# Enclosure_130x95_BPHC.net
KiCad netlist of a schematic drawn in EAGLE
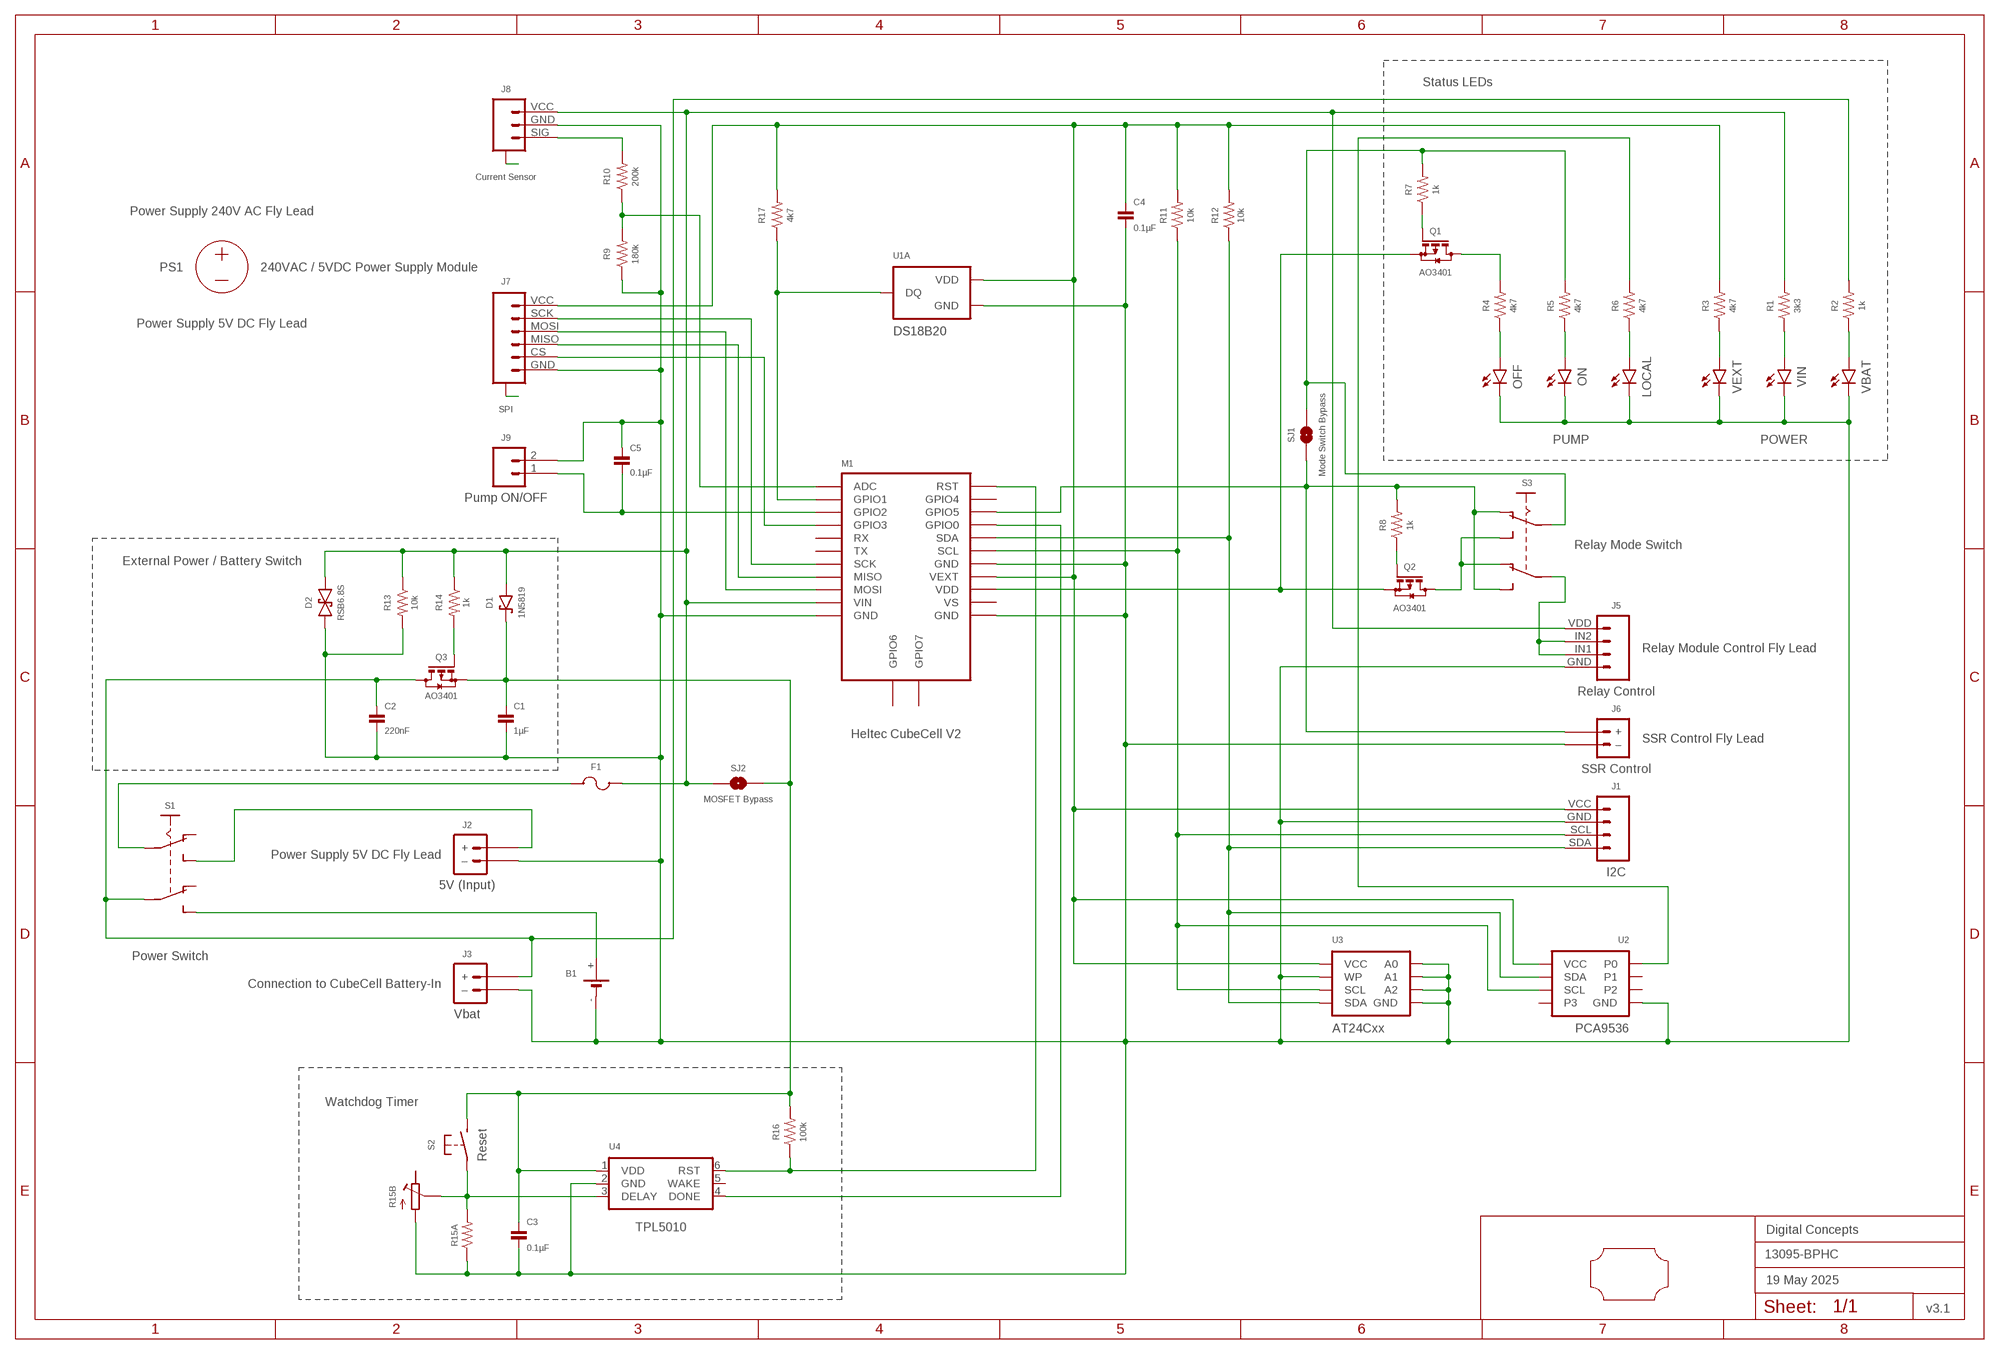
[diagram p0: schematic, sheet 1]

(export (version "E")
  (design (tool "Eeschema 10.0.6"))
  (components
    (comp (ref "B1")
      (value "BATTERY-HOLDER-14500(AA)")
      (footprint "eagle-import:BATTERY-14500")
      (libsource (lib "eagle-import") (part "BATTERY-HOLDER-14500(AA)"))
    )
    (comp (ref "C1")
      (value "1µF")
      (footprint "eagle-import:C0805")
      (libsource (lib "eagle-import") (part "CAPACITOR-0805"))
    )
    (comp (ref "C2")
      (value "220nF")
      (footprint "eagle-import:C0805")
      (libsource (lib "eagle-import") (part "CAPACITOR-0805"))
    )
    (comp (ref "C3")
      (value "0.1µF")
      (footprint "eagle-import:C0805")
      (libsource (lib "eagle-import") (part "CAPACITOR-0805"))
    )
    (comp (ref "C4")
      (value "0.1µF")
      (footprint "eagle-import:C0805")
      (libsource (lib "eagle-import") (part "CAPACITOR-0805"))
    )
    (comp (ref "C5")
      (value "0.1µF")
      (footprint "eagle-import:C0805")
      (libsource (lib "eagle-import") (part "CAPACITOR-0805"))
    )
    (comp (ref "D1")
      (value "1N5819")
      (footprint "eagle-import:SOD-123")
      (libsource (lib "eagle-import") (part "DIODE-SCHOTTKY-1N5819"))
    )
    (comp (ref "D2")
      (value "RSB6.8S")
      (footprint "eagle-import:VMD2")
      (libsource (lib "eagle-import") (part "DIODE-SCHOTTKY-BIDIRECTIONAL"))
    )
    (comp (ref "F1")
      (value "Fuse")
      (footprint "eagle-import:F0805")
      (libsource (lib "eagle-import") (part "MF-PSMF050X-2"))
    )
    (comp (ref "J1")
      (value "I2C")
      (footprint "eagle-import:CONN_04-I2C")
      (libsource (lib "eagle-import") (part "HEADER-1X4-I2C"))
    )
    (comp (ref "J2")
      (value "5V (Input)")
      (footprint "eagle-import:JST-PH2.0-2-VERTICAL-POWER")
      (libsource (lib "eagle-import") (part "JST-PH2.0-2-VERTICAL-POWER"))
    )
    (comp (ref "J3")
      (value "Vbat")
      (footprint "eagle-import:JST-GH1.25-2-HORIZONTAL")
      (libsource (lib "eagle-import") (part "JST-GH1.25-2-HORIZONTAL-POWER"))
    )
    (comp (ref "J5")
      (value "Relay Control")
      (footprint "eagle-import:JST-PH2.0-4-HORIZONTAL-RELAY")
      (libsource (lib "eagle-import") (part "JST-PH2.0-4-HORIZONTAL-RELAY"))
    )
    (comp (ref "J6")
      (value "SSR Control")
      (footprint "eagle-import:JST-PH2.0-2-HORIZONTAL-POWER")
      (libsource (lib "eagle-import") (part "JST-PH2.0-2-H-POWER"))
    )
    (comp (ref "J7")
      (value "SPI")
      (footprint "eagle-import:JST-SH1.0-6-HORIZONTAL-SPI")
      (libsource (lib "eagle-import") (part "JST-SH1.0-6-SMD-HORIZONTAL-SPI"))
    )
    (comp (ref "J8")
      (value "Current Sensor")
      (footprint "eagle-import:JST-SH1.0-3-HORIZONTAL-SIG")
      (libsource (lib "eagle-import") (part "JST-SH1.0-3-SMD-HORIZONTAL-SIG"))
    )
    (comp (ref "J9")
      (value "Pump ON/OFF")
      (footprint "eagle-import:CONN_02-GENERIC")
      (libsource (lib "eagle-import") (part "HEADER-1X2-GENERIC"))
    )
    (comp (ref "LOCAL")
      (value "LEDCHIP-LED0805")
      (footprint "eagle-import:CHIP-LED0805")
      (libsource (lib "eagle-import") (part "LEDCHIP-LED0805"))
    )
    (comp (ref "M1")
      (value "Heltec CubeCell V2")
      (footprint "eagle-import:HELTEC-CUBECELL")
      (libsource (lib "eagle-import") (part "HELTEC-CUBECELL"))
    )
    (comp (ref "OFF")
      (value "LEDCHIP-LED0805")
      (footprint "eagle-import:CHIP-LED0805")
      (libsource (lib "eagle-import") (part "LEDCHIP-LED0805"))
    )
    (comp (ref "ON")
      (value "LEDCHIP-LED0805")
      (footprint "eagle-import:CHIP-LED0805")
      (libsource (lib "eagle-import") (part "LEDCHIP-LED0805"))
    )
    (comp (ref "PCB1")
      (value "PCB-OUTLINE-130X95-HALF-TOP")
      (footprint "eagle-import:PROTO-130X95-OUTLINE-HALF-TOP")
      (libsource (lib "eagle-import") (part "PCB-OUTLINE-130X95-HALF-TOP"))
    )
    (comp (ref "PS1")
      (value "240VAC / 5VDC Power Supply Module")
      (footprint "eagle-import:AC_DC_POWER_SUPPLY")
      (libsource (lib "eagle-import") (part "POWER_SUPPLY_MODULE"))
    )
    (comp (ref "Q1")
      (value "AO3401")
      (footprint "eagle-import:SOT-23")
      (libsource (lib "eagle-import") (part "MOSFET-AO3401"))
    )
    (comp (ref "Q2")
      (value "AO3401")
      (footprint "eagle-import:SOT-23")
      (libsource (lib "eagle-import") (part "MOSFET-AO3401"))
    )
    (comp (ref "Q3")
      (value "AO3401")
      (footprint "eagle-import:SOT-23")
      (libsource (lib "eagle-import") (part "MOSFET-AO3401"))
    )
    (comp (ref "R1")
      (value "3k3")
      (footprint "eagle-import:R0805")
      (libsource (lib "eagle-import") (part "RESISTORR0805"))
    )
    (comp (ref "R2")
      (value "1k")
      (footprint "eagle-import:R0805")
      (libsource (lib "eagle-import") (part "RESISTORR0805"))
    )
    (comp (ref "R3")
      (value "4k7")
      (footprint "eagle-import:R0805")
      (libsource (lib "eagle-import") (part "RESISTORR0805"))
    )
    (comp (ref "R4")
      (value "4k7")
      (footprint "eagle-import:R0805")
      (libsource (lib "eagle-import") (part "RESISTORR0805"))
    )
    (comp (ref "R5")
      (value "4k7")
      (footprint "eagle-import:R0805")
      (libsource (lib "eagle-import") (part "RESISTORR0805"))
    )
    (comp (ref "R6")
      (value "4k7")
      (footprint "eagle-import:R0805")
      (libsource (lib "eagle-import") (part "RESISTORR0805"))
    )
    (comp (ref "R7")
      (value "1k")
      (footprint "eagle-import:R0805")
      (libsource (lib "eagle-import") (part "RESISTORR0805"))
    )
    (comp (ref "R8")
      (value "1k")
      (footprint "eagle-import:R0805")
      (libsource (lib "eagle-import") (part "RESISTORR0805"))
    )
    (comp (ref "R9")
      (value "180k")
      (footprint "eagle-import:R0805")
      (libsource (lib "eagle-import") (part "RESISTORR0805"))
    )
    (comp (ref "R10")
      (value "200k")
      (footprint "eagle-import:R0805")
      (libsource (lib "eagle-import") (part "RESISTORR0805"))
    )
    (comp (ref "R11")
      (value "10k")
      (footprint "eagle-import:R0805")
      (libsource (lib "eagle-import") (part "RESISTORR0805"))
    )
    (comp (ref "R12")
      (value "10k")
      (footprint "eagle-import:R0805")
      (libsource (lib "eagle-import") (part "RESISTORR0805"))
    )
    (comp (ref "R13")
      (value "10k")
      (footprint "eagle-import:R0805")
      (libsource (lib "eagle-import") (part "RESISTORR0805"))
    )
    (comp (ref "R14")
      (value "1k")
      (footprint "eagle-import:R0805")
      (libsource (lib "eagle-import") (part "RESISTORR0805"))
    )
    (comp (ref "R15A")
      (value "RESISTORR0805")
      (footprint "eagle-import:R0805")
      (libsource (lib "eagle-import") (part "RESISTORR0805"))
    )
    (comp (ref "R15B")
      (value "RESISTOR-TRIMM-33")
      (footprint "eagle-import:RTRIM3_3")
      (libsource (lib "eagle-import") (part "RESISTOR-TRIMM-33"))
    )
    (comp (ref "R16")
      (value "100k")
      (footprint "eagle-import:R0805")
      (libsource (lib "eagle-import") (part "RESISTORR0805"))
    )
    (comp (ref "R17")
      (value "4k7")
      (footprint "eagle-import:R0805")
      (libsource (lib "eagle-import") (part "RESISTORR0805"))
    )
    (comp (ref "S1")
      (value "Power Switch")
      (footprint "eagle-import:SWITCH-DPDT-PTH")
      (libsource (lib "eagle-import") (part "SWITCH-SLIDE-DPDT-PTH"))
    )
    (comp (ref "S2")
      (value "Reset")
      (footprint "eagle-import:SWITCH-2-PAD")
      (libsource (lib "eagle-import") (part "SWITCH-MOMENTARY-2-PIN"))
    )
    (comp (ref "S3")
      (value "Relay Mode Switch")
      (footprint "eagle-import:SWITCH-DPDT-SMD")
      (libsource (lib "eagle-import") (part "SWITCH-SLIDE-DPDT-SMT"))
    )
    (comp (ref "SJ1")
      (value "Mode Switch Bypass")
      (footprint "eagle-import:SJ")
      (libsource (lib "eagle-import") (part "SJ"))
    )
    (comp (ref "SJ2")
      (value "MOSFET Bypass")
      (footprint "eagle-import:SJ")
      (libsource (lib "eagle-import") (part "SJ"))
    )
    (comp (ref "U1A")
      (value "DS18B20")
      (footprint "eagle-import:TO-92")
      (fields (field (name "MF") "Maxim Integrated"))
      (libsource (lib "eagle-import") (part "THERMOMETER-DS18B20"))
    )
    (comp (ref "U2")
      (value "PCA9536")
      (footprint "eagle-import:SOP-8")
      (libsource (lib "eagle-import") (part "PCA9536-I2C-GPIO4"))
    )
    (comp (ref "U3")
      (value "AT24Cxx")
      (footprint "eagle-import:SOP-8")
      (libsource (lib "eagle-import") (part "AT24CXX-EEPROM"))
    )
    (comp (ref "U4")
      (value "TPL5010")
      (footprint "eagle-import:SOT-23-6")
      (libsource (lib "eagle-import") (part "TPL5010DDCR"))
    )
    (comp (ref "VBAT")
      (value "LEDCHIP-LED0805")
      (footprint "eagle-import:CHIP-LED0805")
      (libsource (lib "eagle-import") (part "LEDCHIP-LED0805"))
    )
    (comp (ref "VEXT")
      (value "LEDCHIP-LED0805")
      (footprint "eagle-import:CHIP-LED0805")
      (libsource (lib "eagle-import") (part "LEDCHIP-LED0805"))
    )
    (comp (ref "VIN")
      (value "LEDCHIP-LED0805")
      (footprint "eagle-import:CHIP-LED0805")
      (libsource (lib "eagle-import") (part "LEDCHIP-LED0805"))
    )
  )
  (nets
    (net (code "1") (name "Net-(C5-Pad2)") (class "Default")
      (node (ref "C5") (pin "2") (pinfunction "2_2") (pintype "passive"))
      (node (ref "J9") (pin "1") (pinfunction "1_1") (pintype "passive"))
      (node (ref "M1") (pin "GPIO2") (pinfunction "GPIO2_GPIO2") (pintype "bidirectional"))
    )
    (net (code "2") (name "Net-(D2-1)") (class "Default")
      (node (ref "D1") (pin "A") (pinfunction "A_A") (pintype "passive"))
      (node (ref "D2") (pin "P$1") (pinfunction "1_P$1") (pintype "passive"))
      (node (ref "F1") (pin "1") (pinfunction "1_1") (pintype "passive"))
      (node (ref "J5") (pin "VDD") (pinfunction "1_VDD") (pintype "passive"))
      (node (ref "J8") (pin "VCC") (pinfunction "3_VCC") (pintype "passive"))
      (node (ref "M1") (pin "VIN") (pinfunction "VIN_VIN") (pintype "bidirectional"))
      (node (ref "R1") (pin "2") (pinfunction "2_2") (pintype "passive"))
      (node (ref "R13") (pin "1") (pinfunction "1_1") (pintype "passive"))
      (node (ref "R14") (pin "1") (pinfunction "1_1") (pintype "passive"))
      (node (ref "SJ2") (pin "1") (pinfunction "1_1") (pintype "passive"))
    )
    (net (code "3") (name "Net-(D2-2)") (class "Default")
      (node (ref "B1") (pin "-") (pinfunction "-_-") (pintype "power_in"))
      (node (ref "C1") (pin "2") (pinfunction "2_2") (pintype "passive"))
      (node (ref "C2") (pin "2") (pinfunction "2_2") (pintype "passive"))
      (node (ref "C3") (pin "2") (pinfunction "2_2") (pintype "passive"))
      (node (ref "C4") (pin "2") (pinfunction "2_2") (pintype "passive"))
      (node (ref "C5") (pin "1") (pinfunction "1_1") (pintype "passive"))
      (node (ref "D2") (pin "P$2") (pinfunction "2_P$2") (pintype "passive"))
      (node (ref "J1") (pin "GND") (pinfunction "2_GND") (pintype "passive"))
      (node (ref "J2") (pin "-") (pinfunction "–_-") (pintype "power_in"))
      (node (ref "J3") (pin "-") (pinfunction "–_-") (pintype "power_in"))
      (node (ref "J5") (pin "GND") (pinfunction "4_GND") (pintype "passive"))
      (node (ref "J6") (pin "-") (pinfunction "–_-") (pintype "power_in"))
      (node (ref "J7") (pin "GND") (pinfunction "1_GND") (pintype "passive"))
      (node (ref "J8") (pin "GND") (pinfunction "2_GND") (pintype "passive"))
      (node (ref "J9") (pin "2") (pinfunction "2_2") (pintype "passive"))
      (node (ref "LOCAL") (pin "C") (pinfunction "C_C") (pintype "passive"))
      (node (ref "M1") (pin "GND@11") (pinfunction "GND_GND@11") (pintype "bidirectional"))
      (node (ref "M1") (pin "GND@14") (pinfunction "GND_GND@14") (pintype "bidirectional"))
      (node (ref "M1") (pin "GND@18") (pinfunction "GND_GND@18") (pintype "bidirectional"))
      (node (ref "OFF") (pin "C") (pinfunction "C_C") (pintype "passive"))
      (node (ref "ON") (pin "C") (pinfunction "C_C") (pintype "passive"))
      (node (ref "R13") (pin "2") (pinfunction "2_2") (pintype "passive"))
      (node (ref "R15A") (pin "1") (pinfunction "1_1") (pintype "passive"))
      (node (ref "R15B") (pin "1") (pinfunction "A_1") (pintype "passive"))
      (node (ref "R9") (pin "1") (pinfunction "1_1") (pintype "passive"))
      (node (ref "U1A") (pin "1") (pinfunction "GND_1") (pintype "power_in"))
      (node (ref "U2") (pin "4") (pinfunction "GND_4") (pintype "power_in"))
      (node (ref "U3") (pin "1") (pinfunction "A0_1") (pintype "bidirectional"))
      (node (ref "U3") (pin "2") (pinfunction "A1_2") (pintype "bidirectional"))
      (node (ref "U3") (pin "3") (pinfunction "A2_3") (pintype "bidirectional"))
      (node (ref "U3") (pin "4") (pinfunction "GND_4") (pintype "bidirectional"))
      (node (ref "U3") (pin "7") (pinfunction "WP_7") (pintype "bidirectional"))
      (node (ref "U4") (pin "2") (pinfunction "GND_2") (pintype "power_in"))
      (node (ref "VBAT") (pin "C") (pinfunction "C_C") (pintype "passive"))
      (node (ref "VEXT") (pin "C") (pinfunction "C_C") (pintype "passive"))
      (node (ref "VIN") (pin "C") (pinfunction "C_C") (pintype "passive"))
    )
    (net (code "4") (name "Net-(J1-1)") (class "Default")
      (node (ref "C4") (pin "1") (pinfunction "1_1") (pintype "passive"))
      (node (ref "J1") (pin "VCC") (pinfunction "1_VCC") (pintype "passive"))
      (node (ref "J7") (pin "VCC") (pinfunction "6_VCC") (pintype "passive"))
      (node (ref "M1") (pin "VEXT") (pinfunction "VEXT_VEXT") (pintype "bidirectional"))
      (node (ref "R11") (pin "2") (pinfunction "2_2") (pintype "passive"))
      (node (ref "R12") (pin "2") (pinfunction "2_2") (pintype "passive"))
      (node (ref "R17") (pin "2") (pinfunction "2_2") (pintype "passive"))
      (node (ref "R3") (pin "2") (pinfunction "2_2") (pintype "passive"))
      (node (ref "U1A") (pin "3") (pinfunction "VDD_3") (pintype "power_in"))
      (node (ref "U2") (pin "8") (pinfunction "VCC_8") (pintype "power_in"))
      (node (ref "U3") (pin "8") (pinfunction "VCC_8") (pintype "bidirectional"))
    )
    (net (code "5") (name "Net-(J1-3)") (class "Default")
      (node (ref "J1") (pin "SCL") (pinfunction "3_SCL") (pintype "passive"))
      (node (ref "M1") (pin "SCL") (pinfunction "SCL_SCL") (pintype "bidirectional"))
      (node (ref "R11") (pin "1") (pinfunction "1_1") (pintype "passive"))
      (node (ref "U2") (pin "6") (pinfunction "SCL_6") (pintype "bidirectional"))
      (node (ref "U3") (pin "6") (pinfunction "SCL_6") (pintype "bidirectional"))
    )
    (net (code "6") (name "Net-(J1-4)") (class "Default")
      (node (ref "J1") (pin "SDA") (pinfunction "4_SDA") (pintype "passive"))
      (node (ref "M1") (pin "SDA") (pinfunction "SDA_SDA") (pintype "bidirectional"))
      (node (ref "R12") (pin "1") (pinfunction "1_1") (pintype "passive"))
      (node (ref "U2") (pin "7") (pinfunction "SDA_7") (pintype "bidirectional"))
      (node (ref "U3") (pin "5") (pinfunction "SDA_5") (pintype "bidirectional"))
    )
    (net (code "7") (name "Net-(J5-2)") (class "Default")
      (node (ref "J5") (pin "IN1") (pinfunction "3_IN1") (pintype "passive"))
      (node (ref "J5") (pin "IN2") (pinfunction "2_IN2") (pintype "passive"))
      (node (ref "S3") (pin "P$5") (pinfunction "P2_P$5") (pintype "passive"))
    )
    (net (code "8") (name "Net-(J7-2)") (class "Default")
      (node (ref "J7") (pin "CS") (pinfunction "2_CS") (pintype "passive"))
      (node (ref "M1") (pin "GPIO3") (pinfunction "GPIO3_GPIO3") (pintype "bidirectional"))
    )
    (net (code "9") (name "Net-(J7-3)") (class "Default")
      (node (ref "J7") (pin "MISO") (pinfunction "3_MISO") (pintype "passive"))
      (node (ref "M1") (pin "MISO") (pinfunction "MISO_MISO") (pintype "bidirectional"))
    )
    (net (code "10") (name "Net-(J7-4)") (class "Default")
      (node (ref "J7") (pin "MOSI") (pinfunction "4_MOSI") (pintype "passive"))
      (node (ref "M1") (pin "MOSI") (pinfunction "MOSI_MOSI") (pintype "bidirectional"))
    )
    (net (code "11") (name "Net-(J7-5)") (class "Default")
      (node (ref "J7") (pin "SCK") (pinfunction "5_SCK") (pintype "passive"))
      (node (ref "M1") (pin "SCK") (pinfunction "SCK_SCK") (pintype "bidirectional"))
    )
    (net (code "12") (name "Net-(J7-A-PadA@1)") (class "Default")
      (node (ref "J7") (pin "A@1") (pinfunction "A_A@1") (pintype "power_in"))
      (node (ref "J7") (pin "A@6") (pinfunction "A_A@6") (pintype "power_in"))
    )
    (net (code "13") (name "Net-(J8-1)") (class "Default")
      (node (ref "J8") (pin "SIG") (pinfunction "1_SIG") (pintype "passive"))
      (node (ref "R10") (pin "2") (pinfunction "2_2") (pintype "passive"))
    )
    (net (code "14") (name "Net-(J8-A-PadA@1)") (class "Default")
      (node (ref "J8") (pin "A@1") (pinfunction "A_A@1") (pintype "power_in"))
      (node (ref "J8") (pin "A@3") (pinfunction "A_A@3") (pintype "power_in"))
    )
    (net (code "15") (name "Net-(LOCAL-PadA)") (class "Default")
      (node (ref "LOCAL") (pin "A") (pinfunction "A_A") (pintype "passive"))
      (node (ref "R6") (pin "1") (pinfunction "1_1") (pintype "passive"))
    )
    (net (code "16") (name "Net-(M1-PadADC)") (class "Default")
      (node (ref "M1") (pin "ADC") (pinfunction "ADC_ADC") (pintype "bidirectional"))
      (node (ref "R10") (pin "1") (pinfunction "1_1") (pintype "passive"))
      (node (ref "R9") (pin "2") (pinfunction "2_2") (pintype "passive"))
    )
    (net (code "17") (name "Net-(OFF-PadA)") (class "Default")
      (node (ref "OFF") (pin "A") (pinfunction "A_A") (pintype "passive"))
      (node (ref "R4") (pin "1") (pinfunction "1_1") (pintype "passive"))
    )
    (net (code "18") (name "Net-(ON-PadA)") (class "Default")
      (node (ref "ON") (pin "A") (pinfunction "A_A") (pintype "passive"))
      (node (ref "R5") (pin "1") (pinfunction "1_1") (pintype "passive"))
    )
    (net (code "19") (name "Net-(Q1-D)") (class "Default")
      (node (ref "Q1") (pin "3") (pinfunction "D_3") (pintype "passive"))
      (node (ref "R4") (pin "2") (pinfunction "2_2") (pintype "passive"))
    )
    (net (code "20") (name "Net-(Q1-G)") (class "Default")
      (node (ref "Q1") (pin "1") (pinfunction "G_1") (pintype "passive"))
      (node (ref "R7") (pin "1") (pinfunction "1_1") (pintype "passive"))
    )
    (net (code "21") (name "Net-(Q1-S)") (class "Default")
      (node (ref "M1") (pin "VDD") (pinfunction "VDD_VDD") (pintype "bidirectional"))
      (node (ref "Q1") (pin "2") (pinfunction "S_2") (pintype "passive"))
      (node (ref "Q2") (pin "2") (pinfunction "S_2") (pintype "passive"))
    )
    (net (code "22") (name "Net-(Q2-D)") (class "Default")
      (node (ref "Q2") (pin "3") (pinfunction "D_3") (pintype "passive"))
      (node (ref "S3") (pin "P$3") (pinfunction "S1_P$3") (pintype "passive"))
      (node (ref "S3") (pin "P$4") (pinfunction "O2_P$4") (pintype "passive"))
    )
    (net (code "23") (name "Net-(Q2-G)") (class "Default")
      (node (ref "Q2") (pin "1") (pinfunction "G_1") (pintype "passive"))
      (node (ref "R8") (pin "1") (pinfunction "1_1") (pintype "passive"))
    )
    (net (code "24") (name "Net-(Q3-D)") (class "Default")
      (node (ref "C2") (pin "1") (pinfunction "1_1") (pintype "passive"))
      (node (ref "J3") (pin "+") (pinfunction "+_+") (pintype "power_in"))
      (node (ref "Q3") (pin "3") (pinfunction "D_3") (pintype "passive"))
      (node (ref "R2") (pin "2") (pinfunction "2_2") (pintype "passive"))
      (node (ref "S1") (pin "P$5") (pinfunction "P2_P$5") (pintype "passive"))
    )
    (net (code "25") (name "Net-(Q3-G)") (class "Default")
      (node (ref "Q3") (pin "1") (pinfunction "G_1") (pintype "passive"))
      (node (ref "R14") (pin "2") (pinfunction "2_2") (pintype "passive"))
    )
    (net (code "26") (name "Net-(Q3-S)") (class "Default")
      (node (ref "C1") (pin "1") (pinfunction "1_1") (pintype "passive"))
      (node (ref "C3") (pin "1") (pinfunction "1_1") (pintype "passive"))
      (node (ref "D1") (pin "C") (pinfunction "C_C") (pintype "passive"))
      (node (ref "Q3") (pin "2") (pinfunction "S_2") (pintype "passive"))
      (node (ref "R16") (pin "2") (pinfunction "2_2") (pintype "passive"))
      (node (ref "S2") (pin "P$2") (pinfunction "S_P$2") (pintype "passive"))
      (node (ref "SJ2") (pin "2") (pinfunction "2_2") (pintype "passive"))
      (node (ref "U4") (pin "1") (pinfunction "VDD_1") (pintype "power_in"))
    )
    (net (code "27") (name "Net-(R1-Pad1)") (class "Default")
      (node (ref "R1") (pin "1") (pinfunction "1_1") (pintype "passive"))
      (node (ref "VIN") (pin "A") (pinfunction "A_A") (pintype "passive"))
    )
    (net (code "28") (name "Net-(R2-Pad1)") (class "Default")
      (node (ref "R2") (pin "1") (pinfunction "1_1") (pintype "passive"))
      (node (ref "VBAT") (pin "A") (pinfunction "A_A") (pintype "passive"))
    )
    (net (code "29") (name "Net-(R3-Pad1)") (class "Default")
      (node (ref "R3") (pin "1") (pinfunction "1_1") (pintype "passive"))
      (node (ref "VEXT") (pin "A") (pinfunction "A_A") (pintype "passive"))
    )
    (net (code "30") (name "Net-(R15B-S)") (class "Default")
      (node (ref "R15A") (pin "2") (pinfunction "2_2") (pintype "passive"))
      (node (ref "R15B") (pin "2") (pinfunction "S_2") (pintype "passive"))
      (node (ref "S2") (pin "P$1") (pinfunction "P_P$1") (pintype "passive"))
      (node (ref "U4") (pin "3") (pinfunction "DELAY_3") (pintype "input"))
    )
    (net (code "31") (name "Net-(S1-P1)") (class "Default")
      (node (ref "F1") (pin "2") (pinfunction "2_2") (pintype "passive"))
      (node (ref "S1") (pin "P$2") (pinfunction "P1_P$2") (pintype "passive"))
    )
    (net (code "32") (name "Net-(S1-S1)") (class "Default")
      (node (ref "J2") (pin "+") (pinfunction "+_+") (pintype "power_in"))
      (node (ref "S1") (pin "P$3") (pinfunction "S1_P$3") (pintype "passive"))
    )
    (net (code "33") (name "Net-(S1-S2)") (class "Default")
      (node (ref "B1") (pin "+") (pinfunction "+_+") (pintype "power_in"))
      (node (ref "S1") (pin "P$6") (pinfunction "S2_P$6") (pintype "passive"))
    )
    (net (code "34") (name "Net-(S3-O1)") (class "Default")
      (node (ref "J6") (pin "+") (pinfunction "+_+") (pintype "power_in"))
      (node (ref "M1") (pin "GPIO5") (pinfunction "GPIO5_GPIO5") (pintype "bidirectional"))
      (node (ref "R8") (pin "2") (pinfunction "2_2") (pintype "passive"))
      (node (ref "S3") (pin "P$1") (pinfunction "O1_P$1") (pintype "passive"))
      (node (ref "S3") (pin "P$6") (pinfunction "S2_P$6") (pintype "passive"))
      (node (ref "SJ1") (pin "1") (pinfunction "1_1") (pintype "passive"))
    )
    (net (code "35") (name "Net-(S3-P1)") (class "Default")
      (node (ref "R5") (pin "2") (pinfunction "2_2") (pintype "passive"))
      (node (ref "R7") (pin "2") (pinfunction "2_2") (pintype "passive"))
      (node (ref "S3") (pin "P$2") (pinfunction "P1_P$2") (pintype "passive"))
      (node (ref "SJ1") (pin "2") (pinfunction "2_2") (pintype "passive"))
    )
    (net (code "36") (name "Net-(U1A-DQ)") (class "Default")
      (node (ref "M1") (pin "GPIO1") (pinfunction "GPIO1_GPIO1") (pintype "bidirectional"))
      (node (ref "R17") (pin "1") (pinfunction "1_1") (pintype "passive"))
      (node (ref "U1A") (pin "2") (pinfunction "DQ_2") (pintype "bidirectional"))
    )
    (net (code "37") (name "Net-(U2-P0)") (class "Default")
      (node (ref "R6") (pin "2") (pinfunction "2_2") (pintype "passive"))
      (node (ref "U2") (pin "1") (pinfunction "P0_1") (pintype "bidirectional"))
    )
    (net (code "38") (name "Net-(U4-DONE)") (class "Default")
      (node (ref "M1") (pin "GPIO0") (pinfunction "GPIO0_GPIO0") (pintype "bidirectional"))
      (node (ref "U4") (pin "4") (pinfunction "DONE_4") (pintype "input"))
    )
    (net (code "39") (name "Net-(U4-RST)") (class "Default")
      (node (ref "M1") (pin "RST") (pinfunction "RST_RST") (pintype "bidirectional"))
      (node (ref "R16") (pin "1") (pinfunction "1_1") (pintype "passive"))
      (node (ref "U4") (pin "6") (pinfunction "RST_6") (pintype "output"))
    )
    (net (code "40") (name "unconnected-(M1-PadGPIO4)") (class "Default")
      (node (ref "M1") (pin "GPIO4") (pinfunction "GPIO4_GPIO4") (pintype "bidirectional"))
    )
    (net (code "41") (name "unconnected-(M1-PadGPIO6)") (class "Default")
      (node (ref "M1") (pin "GPIO6") (pinfunction "GPIO6_GPIO6") (pintype "bidirectional"))
    )
    (net (code "42") (name "unconnected-(M1-PadGPIO7)") (class "Default")
      (node (ref "M1") (pin "GPIO7") (pinfunction "GPIO7_GPIO7") (pintype "bidirectional"))
    )
    (net (code "43") (name "unconnected-(M1-PadRX)") (class "Default")
      (node (ref "M1") (pin "RX") (pinfunction "RX_RX") (pintype "bidirectional"))
    )
    (net (code "44") (name "unconnected-(M1-PadTX)") (class "Default")
      (node (ref "M1") (pin "TX") (pinfunction "TX_TX") (pintype "bidirectional"))
    )
    (net (code "45") (name "unconnected-(M1-PadVS)") (class "Default")
      (node (ref "M1") (pin "VS") (pinfunction "VS_VS") (pintype "bidirectional"))
    )
    (net (code "46") (name "unconnected-(R15B-E-Pad3)") (class "Default")
      (node (ref "R15B") (pin "3") (pinfunction "E_3") (pintype "passive"))
    )
    (net (code "47") (name "unconnected-(S1-O1-PadP$1)") (class "Default")
      (node (ref "S1") (pin "P$1") (pinfunction "O1_P$1") (pintype "passive"))
    )
    (net (code "48") (name "unconnected-(S1-O2-PadP$4)") (class "Default")
      (node (ref "S1") (pin "P$4") (pinfunction "O2_P$4") (pintype "passive"))
    )
    (net (code "49") (name "unconnected-(U2-P1-Pad2)") (class "Default")
      (node (ref "U2") (pin "2") (pinfunction "P1_2") (pintype "bidirectional"))
    )
    (net (code "50") (name "unconnected-(U2-P2-Pad3)") (class "Default")
      (node (ref "U2") (pin "3") (pinfunction "P2_3") (pintype "bidirectional"))
    )
    (net (code "51") (name "unconnected-(U2-P3-Pad5)") (class "Default")
      (node (ref "U2") (pin "5") (pinfunction "P3_5") (pintype "bidirectional"))
    )
    (net (code "52") (name "unconnected-(U4-WAKE-Pad5)") (class "Default")
      (node (ref "U4") (pin "5") (pinfunction "WAKE_5") (pintype "output"))
    )
  )
)
